# schematic.net
KiCad netlist of a schematic drawn in EAGLE
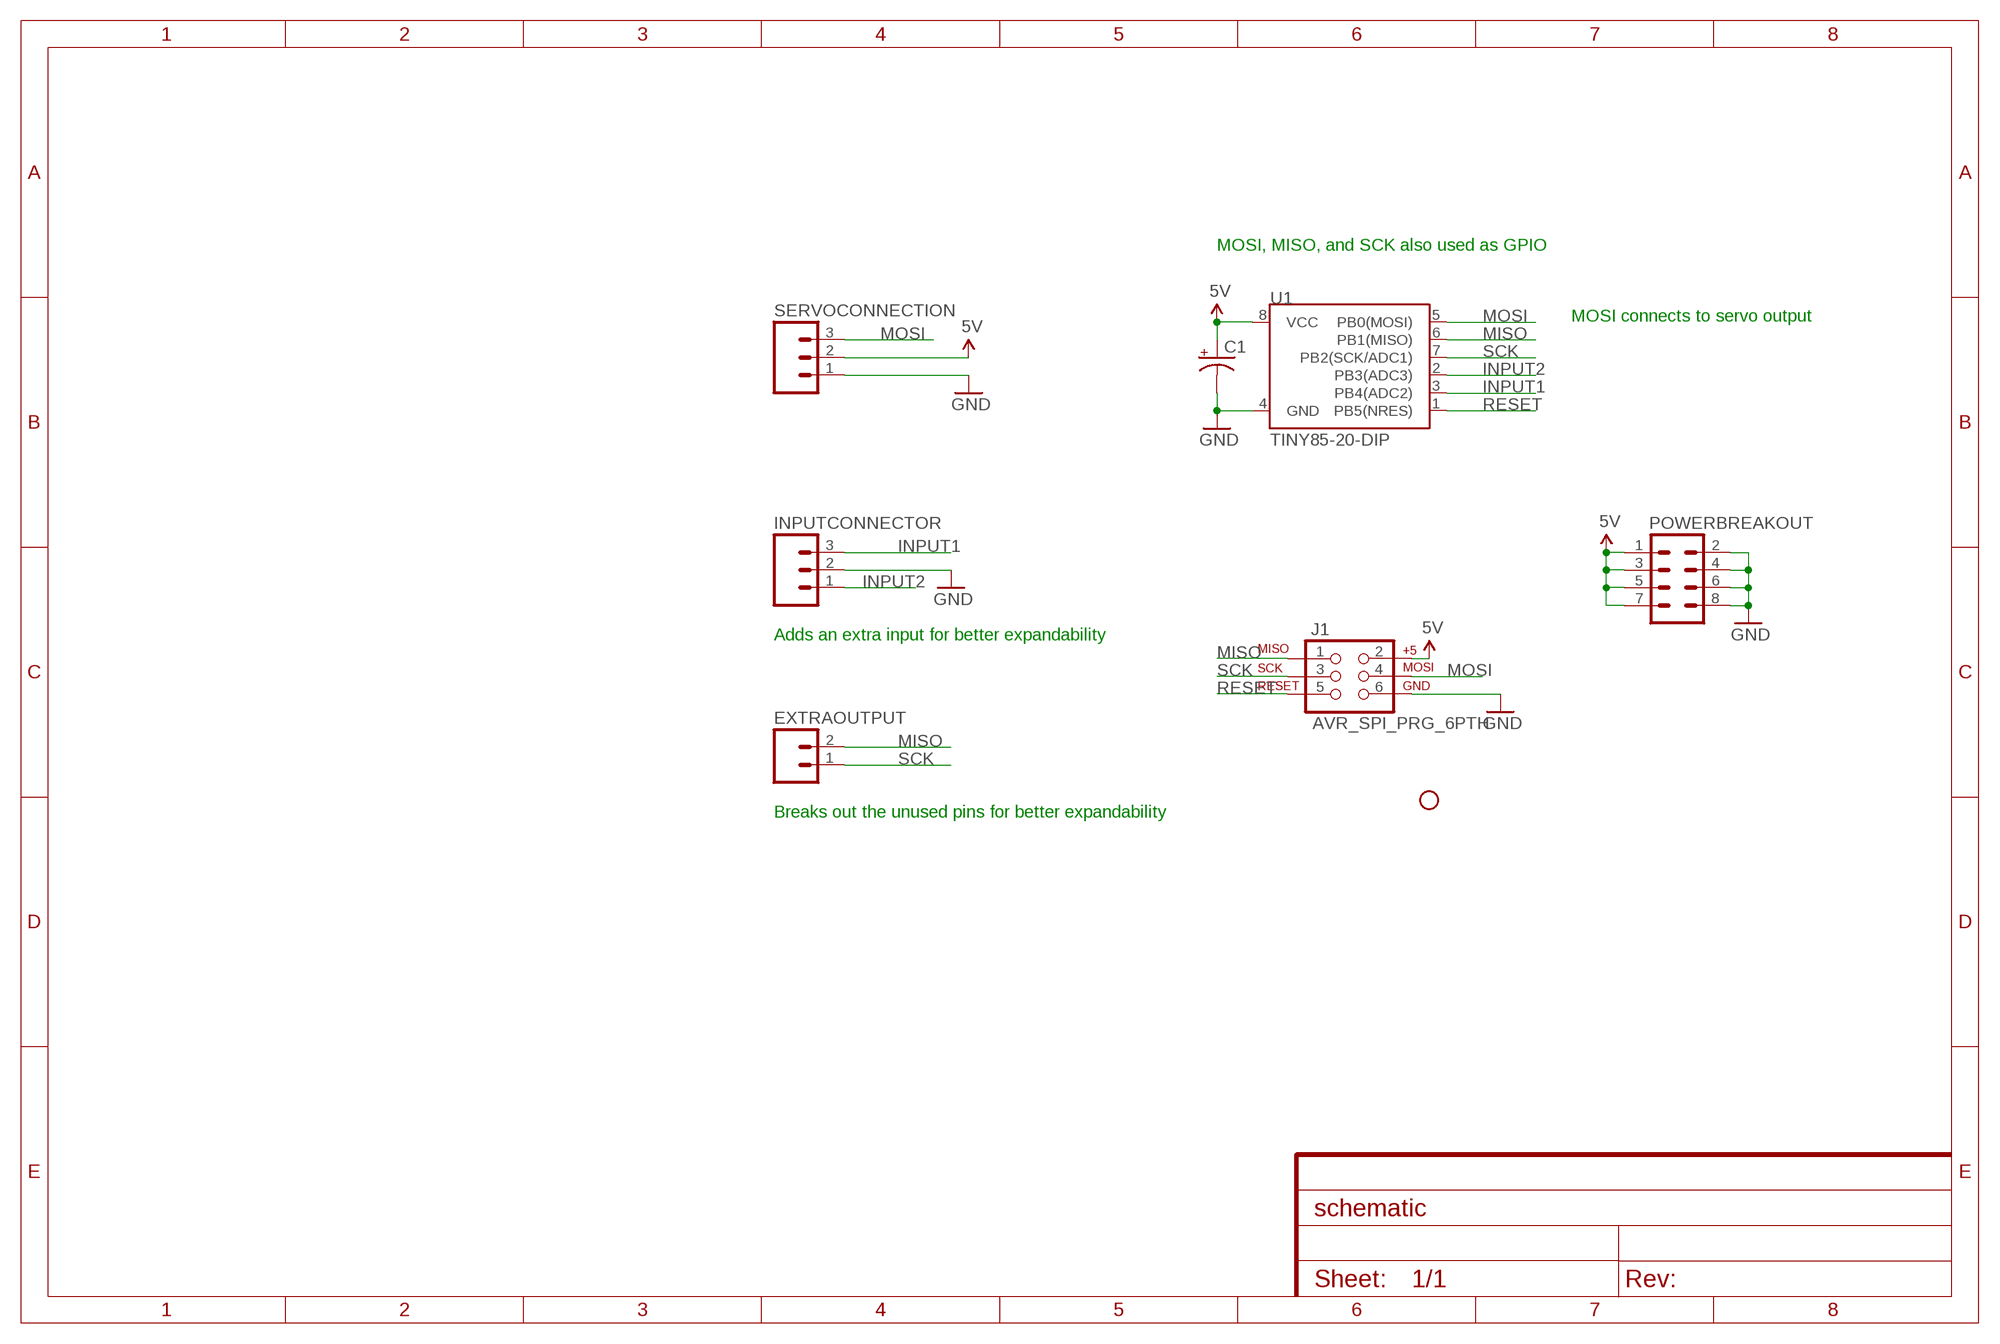
[diagram p0: schematic, sheet 1]

(export (version "E")
  (design (tool "Eeschema 10.0.6"))
  (components
    (comp (ref "C1")
      (value "10UF-25V-20%(PTH)")
      (footprint "eagle-import:CPOL-RADIAL-10UF-25V")
      (libsource (lib "eagle-import") (part "10UF-25V-20%(PTH)"))
    )
    (comp (ref "EXTRAOUTPUT")
      (value "M02PTH")
      (footprint "eagle-import:1X02")
      (libsource (lib "eagle-import") (part "M02PTH"))
    )
    (comp (ref "H1")
      (value "STAND-OFF")
      (footprint "eagle-import:STAND-OFF")
      (libsource (lib "eagle-import") (part "STAND-OFF"))
    )
    (comp (ref "INPUTCONNECTOR")
      (value "M03PTH")
      (footprint "eagle-import:1X03")
      (libsource (lib "eagle-import") (part "M03PTH"))
    )
    (comp (ref "J1")
      (value "AVR_SPI_PRG_6PTH")
      (footprint "eagle-import:2X3")
      (libsource (lib "eagle-import") (part "AVR_SPI_PRG_6PTH"))
    )
    (comp (ref "POWERBREAKOUT")
      (value "M04X2")
      (footprint "eagle-import:2X4")
      (libsource (lib "eagle-import") (part "M04X2"))
    )
    (comp (ref "SERVOCONNECTION")
      (value "M03PTH")
      (footprint "eagle-import:1X03")
      (libsource (lib "eagle-import") (part "M03PTH"))
    )
    (comp (ref "U1")
      (value "TINY85-20-DIP")
      (footprint "eagle-import:DIP08")
      (libsource (lib "eagle-import") (part "ATTINY45TINY85-20-DIP"))
    )
  )
  (nets
    (net (code "1") (name "/INPUT1") (class "Default")
      (node (ref "INPUTCONNECTOR") (pin "3") (pinfunction "3_3") (pintype "passive"))
      (node (ref "U1") (pin "3") (pinfunction "PB4(ADC2)_3") (pintype "bidirectional"))
    )
    (net (code "2") (name "/INPUT2") (class "Default")
      (node (ref "INPUTCONNECTOR") (pin "1") (pinfunction "1_1") (pintype "passive"))
      (node (ref "U1") (pin "2") (pinfunction "PB3(ADC3)_2") (pintype "bidirectional"))
    )
    (net (code "3") (name "/MISO") (class "Default")
      (node (ref "EXTRAOUTPUT") (pin "2") (pinfunction "2_2") (pintype "passive"))
      (node (ref "J1") (pin "1") (pinfunction "1_1") (pintype "passive"))
      (node (ref "U1") (pin "6") (pinfunction "PB1(MISO)_6") (pintype "bidirectional"))
    )
    (net (code "4") (name "/MOSI") (class "Default")
      (node (ref "J1") (pin "4") (pinfunction "4_4") (pintype "passive"))
      (node (ref "SERVOCONNECTION") (pin "3") (pinfunction "3_3") (pintype "passive"))
      (node (ref "U1") (pin "5") (pinfunction "PB0(MOSI)_5") (pintype "bidirectional"))
    )
    (net (code "5") (name "/RESET") (class "Default")
      (node (ref "J1") (pin "5") (pinfunction "5_5") (pintype "passive"))
      (node (ref "U1") (pin "1") (pinfunction "PB5(NRES)_1") (pintype "bidirectional"))
    )
    (net (code "6") (name "/SCK") (class "Default")
      (node (ref "EXTRAOUTPUT") (pin "1") (pinfunction "1_1") (pintype "passive"))
      (node (ref "J1") (pin "3") (pinfunction "3_3") (pintype "passive"))
      (node (ref "U1") (pin "7") (pinfunction "PB2(SCK/ADC1)_7") (pintype "bidirectional"))
    )
    (net (code "7") (name "5V") (class "Default")
      (node (ref "C1") (pin "1") (pinfunction "+_1") (pintype "passive"))
      (node (ref "J1") (pin "2") (pinfunction "2_2") (pintype "passive"))
      (node (ref "POWERBREAKOUT") (pin "1") (pinfunction "1_1") (pintype "passive"))
      (node (ref "POWERBREAKOUT") (pin "3") (pinfunction "3_3") (pintype "passive"))
      (node (ref "POWERBREAKOUT") (pin "5") (pinfunction "5_5") (pintype "passive"))
      (node (ref "POWERBREAKOUT") (pin "7") (pinfunction "7_7") (pintype "passive"))
      (node (ref "SERVOCONNECTION") (pin "2") (pinfunction "2_2") (pintype "passive"))
      (node (ref "U1") (pin "8") (pinfunction "VCC_8") (pintype "bidirectional"))
    )
    (net (code "8") (name "GND") (class "Default")
      (node (ref "C1") (pin "2") (pinfunction "-_2") (pintype "passive"))
      (node (ref "INPUTCONNECTOR") (pin "2") (pinfunction "2_2") (pintype "passive"))
      (node (ref "J1") (pin "6") (pinfunction "6_6") (pintype "passive"))
      (node (ref "POWERBREAKOUT") (pin "2") (pinfunction "2_2") (pintype "passive"))
      (node (ref "POWERBREAKOUT") (pin "4") (pinfunction "4_4") (pintype "passive"))
      (node (ref "POWERBREAKOUT") (pin "6") (pinfunction "6_6") (pintype "passive"))
      (node (ref "POWERBREAKOUT") (pin "8") (pinfunction "8_8") (pintype "passive"))
      (node (ref "SERVOCONNECTION") (pin "1") (pinfunction "1_1") (pintype "passive"))
      (node (ref "U1") (pin "4") (pinfunction "GND_4") (pintype "bidirectional"))
    )
  )
)
